# Enconder_Part3.net
KiCad netlist of a schematic drawn in Altium Designer
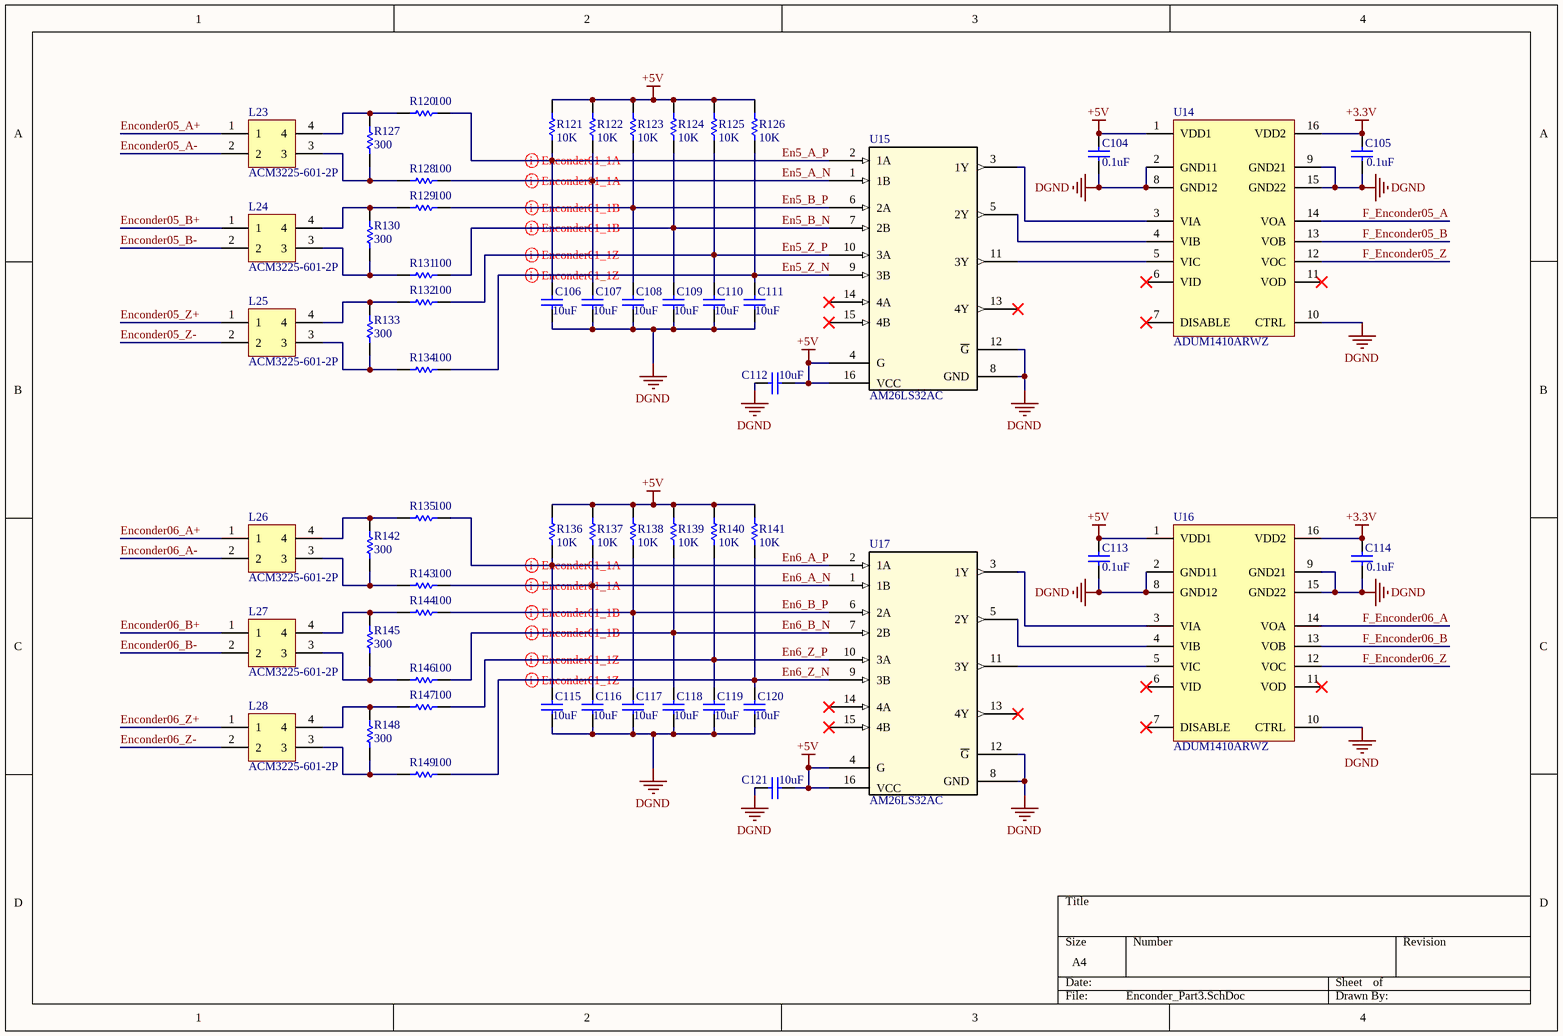
[diagram p0: Enconder_Part3.SchDoc]

(export (version "E")
  (design (tool "Eeschema 10.0.6"))
  (components
    (comp (ref "C104")
      (value "0.1uF")
      (footprint "1608[0603]")
      (description "Capacitor")
      (fields (field (name "Comment") "Cap") (field (name "PUBLISHER") "Altium Limited"))
      (libsource (lib "Miscellaneous Devices") (part "Cap"))
    )
    (comp (ref "C105")
      (value "0.1uF")
      (footprint "1608[0603]")
      (description "Capacitor")
      (fields (field (name "Comment") "Cap") (field (name "PUBLISHER") "Altium Limited"))
      (libsource (lib "Miscellaneous Devices") (part "Cap"))
    )
    (comp (ref "C106")
      (value "10uF")
      (footprint "1608[0603]")
      (description "Capacitor")
      (fields (field (name "Comment") "Cap") (field (name "PUBLISHER") "Altium Limited"))
      (libsource (lib "Miscellaneous Devices") (part "Cap"))
    )
    (comp (ref "C107")
      (value "10uF")
      (footprint "1608[0603]")
      (description "Capacitor")
      (fields (field (name "Comment") "Cap") (field (name "PUBLISHER") "Altium Limited"))
      (libsource (lib "Miscellaneous Devices") (part "Cap"))
    )
    (comp (ref "C108")
      (value "10uF")
      (footprint "1608[0603]")
      (description "Capacitor")
      (fields (field (name "Comment") "Cap") (field (name "PUBLISHER") "Altium Limited"))
      (libsource (lib "Miscellaneous Devices") (part "Cap"))
    )
    (comp (ref "C109")
      (value "10uF")
      (footprint "1608[0603]")
      (description "Capacitor")
      (fields (field (name "Comment") "Cap") (field (name "PUBLISHER") "Altium Limited"))
      (libsource (lib "Miscellaneous Devices") (part "Cap"))
    )
    (comp (ref "C110")
      (value "10uF")
      (footprint "1608[0603]")
      (description "Capacitor")
      (fields (field (name "Comment") "Cap") (field (name "PUBLISHER") "Altium Limited"))
      (libsource (lib "Miscellaneous Devices") (part "Cap"))
    )
    (comp (ref "C111")
      (value "10uF")
      (footprint "1608[0603]")
      (description "Capacitor")
      (fields (field (name "Comment") "Cap") (field (name "PUBLISHER") "Altium Limited"))
      (libsource (lib "Miscellaneous Devices") (part "Cap"))
    )
    (comp (ref "C112")
      (value "10uF")
      (footprint "1608[0603]")
      (description "Capacitor")
      (fields (field (name "Comment") "Cap") (field (name "PUBLISHER") "Altium Limited"))
      (libsource (lib "Miscellaneous Devices") (part "Cap"))
    )
    (comp (ref "C113")
      (value "0.1uF")
      (footprint "1608[0603]")
      (description "Capacitor")
      (fields (field (name "Comment") "Cap") (field (name "PUBLISHER") "Altium Limited"))
      (libsource (lib "Miscellaneous Devices") (part "Cap"))
    )
    (comp (ref "C114")
      (value "0.1uF")
      (footprint "1608[0603]")
      (description "Capacitor")
      (fields (field (name "Comment") "Cap") (field (name "PUBLISHER") "Altium Limited"))
      (libsource (lib "Miscellaneous Devices") (part "Cap"))
    )
    (comp (ref "C115")
      (value "10uF")
      (footprint "1608[0603]")
      (description "Capacitor")
      (fields (field (name "Comment") "Cap") (field (name "PUBLISHER") "Altium Limited"))
      (libsource (lib "Miscellaneous Devices") (part "Cap"))
    )
    (comp (ref "C116")
      (value "10uF")
      (footprint "1608[0603]")
      (description "Capacitor")
      (fields (field (name "Comment") "Cap") (field (name "PUBLISHER") "Altium Limited"))
      (libsource (lib "Miscellaneous Devices") (part "Cap"))
    )
    (comp (ref "C117")
      (value "10uF")
      (footprint "1608[0603]")
      (description "Capacitor")
      (fields (field (name "Comment") "Cap") (field (name "PUBLISHER") "Altium Limited"))
      (libsource (lib "Miscellaneous Devices") (part "Cap"))
    )
    (comp (ref "C118")
      (value "10uF")
      (footprint "1608[0603]")
      (description "Capacitor")
      (fields (field (name "Comment") "Cap") (field (name "PUBLISHER") "Altium Limited"))
      (libsource (lib "Miscellaneous Devices") (part "Cap"))
    )
    (comp (ref "C119")
      (value "10uF")
      (footprint "1608[0603]")
      (description "Capacitor")
      (fields (field (name "Comment") "Cap") (field (name "PUBLISHER") "Altium Limited"))
      (libsource (lib "Miscellaneous Devices") (part "Cap"))
    )
    (comp (ref "C120")
      (value "10uF")
      (footprint "1608[0603]")
      (description "Capacitor")
      (fields (field (name "Comment") "Cap") (field (name "PUBLISHER") "Altium Limited"))
      (libsource (lib "Miscellaneous Devices") (part "Cap"))
    )
    (comp (ref "C121")
      (value "10uF")
      (footprint "1608[0603]")
      (description "Capacitor")
      (fields (field (name "Comment") "Cap") (field (name "PUBLISHER") "Altium Limited"))
      (libsource (lib "Miscellaneous Devices") (part "Cap"))
    )
    (comp (ref "L23")
      (value "ACM3225-601-2P")
      (footprint "ACM3225-601-2P")
      (libsource (lib "DSP_FPGA_Lib") (part "ACM3225-601-2P"))
    )
    (comp (ref "L24")
      (value "ACM3225-601-2P")
      (footprint "ACM3225-601-2P")
      (libsource (lib "DSP_FPGA_Lib") (part "ACM3225-601-2P"))
    )
    (comp (ref "L25")
      (value "ACM3225-601-2P")
      (footprint "ACM3225-601-2P")
      (libsource (lib "DSP_FPGA_Lib") (part "ACM3225-601-2P"))
    )
    (comp (ref "L26")
      (value "ACM3225-601-2P")
      (footprint "ACM3225-601-2P")
      (libsource (lib "DSP_FPGA_Lib") (part "ACM3225-601-2P"))
    )
    (comp (ref "L27")
      (value "ACM3225-601-2P")
      (footprint "ACM3225-601-2P")
      (libsource (lib "DSP_FPGA_Lib") (part "ACM3225-601-2P"))
    )
    (comp (ref "L28")
      (value "ACM3225-601-2P")
      (footprint "ACM3225-601-2P")
      (libsource (lib "DSP_FPGA_Lib") (part "ACM3225-601-2P"))
    )
    (comp (ref "R120")
      (value "100")
      (footprint "1608[0603]")
      (description "Resistor")
      (fields (field (name "Comment") "Res1") (field (name "PUBLISHER") "Altium Limited"))
      (libsource (lib "Miscellaneous Devices") (part "Res1"))
    )
    (comp (ref "R121")
      (value "10K")
      (footprint "1608[0603]")
      (description "Resistor")
      (fields (field (name "Comment") "Res1") (field (name "PUBLISHER") "Altium Limited"))
      (libsource (lib "Miscellaneous Devices") (part "Res1"))
    )
    (comp (ref "R122")
      (value "10K")
      (footprint "1608[0603]")
      (description "Resistor")
      (fields (field (name "Comment") "Res1") (field (name "PUBLISHER") "Altium Limited"))
      (libsource (lib "Miscellaneous Devices") (part "Res1"))
    )
    (comp (ref "R123")
      (value "10K")
      (footprint "1608[0603]")
      (description "Resistor")
      (fields (field (name "Comment") "Res1") (field (name "PUBLISHER") "Altium Limited"))
      (libsource (lib "Miscellaneous Devices") (part "Res1"))
    )
    (comp (ref "R124")
      (value "10K")
      (footprint "1608[0603]")
      (description "Resistor")
      (fields (field (name "Comment") "Res1") (field (name "PUBLISHER") "Altium Limited"))
      (libsource (lib "Miscellaneous Devices") (part "Res1"))
    )
    (comp (ref "R125")
      (value "10K")
      (footprint "1608[0603]")
      (description "Resistor")
      (fields (field (name "Comment") "Res1") (field (name "PUBLISHER") "Altium Limited"))
      (libsource (lib "Miscellaneous Devices") (part "Res1"))
    )
    (comp (ref "R126")
      (value "10K")
      (footprint "1608[0603]")
      (description "Resistor")
      (fields (field (name "Comment") "Res1") (field (name "PUBLISHER") "Altium Limited"))
      (libsource (lib "Miscellaneous Devices") (part "Res1"))
    )
    (comp (ref "R127")
      (value "300")
      (footprint "1608[0603]")
      (description "Resistor")
      (fields (field (name "Comment") "Res1") (field (name "PUBLISHER") "Altium Limited"))
      (libsource (lib "Miscellaneous Devices") (part "Res1"))
    )
    (comp (ref "R128")
      (value "100")
      (footprint "1608[0603]")
      (description "Resistor")
      (fields (field (name "Comment") "Res1") (field (name "PUBLISHER") "Altium Limited"))
      (libsource (lib "Miscellaneous Devices") (part "Res1"))
    )
    (comp (ref "R129")
      (value "100")
      (footprint "1608[0603]")
      (description "Resistor")
      (fields (field (name "Comment") "Res1") (field (name "PUBLISHER") "Altium Limited"))
      (libsource (lib "Miscellaneous Devices") (part "Res1"))
    )
    (comp (ref "R130")
      (value "300")
      (footprint "1608[0603]")
      (description "Resistor")
      (fields (field (name "Comment") "Res1") (field (name "PUBLISHER") "Altium Limited"))
      (libsource (lib "Miscellaneous Devices") (part "Res1"))
    )
    (comp (ref "R131")
      (value "100")
      (footprint "1608[0603]")
      (description "Resistor")
      (fields (field (name "Comment") "Res1") (field (name "PUBLISHER") "Altium Limited"))
      (libsource (lib "Miscellaneous Devices") (part "Res1"))
    )
    (comp (ref "R132")
      (value "100")
      (footprint "1608[0603]")
      (description "Resistor")
      (fields (field (name "Comment") "Res1") (field (name "PUBLISHER") "Altium Limited"))
      (libsource (lib "Miscellaneous Devices") (part "Res1"))
    )
    (comp (ref "R133")
      (value "300")
      (footprint "1608[0603]")
      (description "Resistor")
      (fields (field (name "Comment") "Res1") (field (name "PUBLISHER") "Altium Limited"))
      (libsource (lib "Miscellaneous Devices") (part "Res1"))
    )
    (comp (ref "R134")
      (value "100")
      (footprint "1608[0603]")
      (description "Resistor")
      (fields (field (name "Comment") "Res1") (field (name "PUBLISHER") "Altium Limited"))
      (libsource (lib "Miscellaneous Devices") (part "Res1"))
    )
    (comp (ref "R135")
      (value "100")
      (footprint "1608[0603]")
      (description "Resistor")
      (fields (field (name "Comment") "Res1") (field (name "PUBLISHER") "Altium Limited"))
      (libsource (lib "Miscellaneous Devices") (part "Res1"))
    )
    (comp (ref "R136")
      (value "10K")
      (footprint "1608[0603]")
      (description "Resistor")
      (fields (field (name "Comment") "Res1") (field (name "PUBLISHER") "Altium Limited"))
      (libsource (lib "Miscellaneous Devices") (part "Res1"))
    )
    (comp (ref "R137")
      (value "10K")
      (footprint "1608[0603]")
      (description "Resistor")
      (fields (field (name "Comment") "Res1") (field (name "PUBLISHER") "Altium Limited"))
      (libsource (lib "Miscellaneous Devices") (part "Res1"))
    )
    (comp (ref "R138")
      (value "10K")
      (footprint "1608[0603]")
      (description "Resistor")
      (fields (field (name "Comment") "Res1") (field (name "PUBLISHER") "Altium Limited"))
      (libsource (lib "Miscellaneous Devices") (part "Res1"))
    )
    (comp (ref "R139")
      (value "10K")
      (footprint "1608[0603]")
      (description "Resistor")
      (fields (field (name "Comment") "Res1") (field (name "PUBLISHER") "Altium Limited"))
      (libsource (lib "Miscellaneous Devices") (part "Res1"))
    )
    (comp (ref "R140")
      (value "10K")
      (footprint "1608[0603]")
      (description "Resistor")
      (fields (field (name "Comment") "Res1") (field (name "PUBLISHER") "Altium Limited"))
      (libsource (lib "Miscellaneous Devices") (part "Res1"))
    )
    (comp (ref "R141")
      (value "10K")
      (footprint "1608[0603]")
      (description "Resistor")
      (fields (field (name "Comment") "Res1") (field (name "PUBLISHER") "Altium Limited"))
      (libsource (lib "Miscellaneous Devices") (part "Res1"))
    )
    (comp (ref "R142")
      (value "300")
      (footprint "1608[0603]")
      (description "Resistor")
      (fields (field (name "Comment") "Res1") (field (name "PUBLISHER") "Altium Limited"))
      (libsource (lib "Miscellaneous Devices") (part "Res1"))
    )
    (comp (ref "R143")
      (value "100")
      (footprint "1608[0603]")
      (description "Resistor")
      (fields (field (name "Comment") "Res1") (field (name "PUBLISHER") "Altium Limited"))
      (libsource (lib "Miscellaneous Devices") (part "Res1"))
    )
    (comp (ref "R144")
      (value "100")
      (footprint "1608[0603]")
      (description "Resistor")
      (fields (field (name "Comment") "Res1") (field (name "PUBLISHER") "Altium Limited"))
      (libsource (lib "Miscellaneous Devices") (part "Res1"))
    )
    (comp (ref "R145")
      (value "300")
      (footprint "1608[0603]")
      (description "Resistor")
      (fields (field (name "Comment") "Res1") (field (name "PUBLISHER") "Altium Limited"))
      (libsource (lib "Miscellaneous Devices") (part "Res1"))
    )
    (comp (ref "R146")
      (value "100")
      (footprint "1608[0603]")
      (description "Resistor")
      (fields (field (name "Comment") "Res1") (field (name "PUBLISHER") "Altium Limited"))
      (libsource (lib "Miscellaneous Devices") (part "Res1"))
    )
    (comp (ref "R147")
      (value "100")
      (footprint "1608[0603]")
      (description "Resistor")
      (fields (field (name "Comment") "Res1") (field (name "PUBLISHER") "Altium Limited"))
      (libsource (lib "Miscellaneous Devices") (part "Res1"))
    )
    (comp (ref "R148")
      (value "300")
      (footprint "1608[0603]")
      (description "Resistor")
      (fields (field (name "Comment") "Res1") (field (name "PUBLISHER") "Altium Limited"))
      (libsource (lib "Miscellaneous Devices") (part "Res1"))
    )
    (comp (ref "R149")
      (value "100")
      (footprint "1608[0603]")
      (description "Resistor")
      (fields (field (name "Comment") "Res1") (field (name "PUBLISHER") "Altium Limited"))
      (libsource (lib "Miscellaneous Devices") (part "Res1"))
    )
    (comp (ref "U14")
      (value "ADUM1410ARWZ")
      (footprint "ADUM1410ARWZ_SOIC")
      (libsource (lib "DSP_FPGA_Lib") (part "ADUM1410ARWZ"))
    )
    (comp (ref "U15")
      (value "AM26LS32AC")
      (footprint "AM26LS32AC_SOP")
      (libsource (lib "DSP_FPGA_Lib") (part "AM26LS32AC"))
    )
    (comp (ref "U16")
      (value "ADUM1410ARWZ")
      (footprint "ADUM1410ARWZ_SOIC")
      (libsource (lib "DSP_FPGA_Lib") (part "ADUM1410ARWZ"))
    )
    (comp (ref "U17")
      (value "AM26LS32AC")
      (footprint "AM26LS32AC_SOP")
      (libsource (lib "DSP_FPGA_Lib") (part "AM26LS32AC"))
    )
  )
  (nets
    (net (code "1") (name "+3.3V") (class "Default")
      (node (ref "C105") (pin "2") (pinfunction "2_2") (pintype "passive"))
      (node (ref "C114") (pin "2") (pinfunction "2_2") (pintype "passive"))
      (node (ref "U14") (pin "16") (pinfunction "VDD2_16") (pintype "passive"))
      (node (ref "U16") (pin "16") (pinfunction "VDD2_16") (pintype "passive"))
    )
    (net (code "2") (name "+5V") (class "Default")
      (node (ref "C104") (pin "2") (pinfunction "2_2") (pintype "passive"))
      (node (ref "C112") (pin "1") (pinfunction "1_1") (pintype "passive"))
      (node (ref "C113") (pin "2") (pinfunction "2_2") (pintype "passive"))
      (node (ref "C121") (pin "1") (pinfunction "1_1") (pintype "passive"))
      (node (ref "R121") (pin "2") (pinfunction "2_2") (pintype "passive"))
      (node (ref "R122") (pin "2") (pinfunction "2_2") (pintype "passive"))
      (node (ref "R123") (pin "2") (pinfunction "2_2") (pintype "passive"))
      (node (ref "R124") (pin "2") (pinfunction "2_2") (pintype "passive"))
      (node (ref "R125") (pin "2") (pinfunction "2_2") (pintype "passive"))
      (node (ref "R126") (pin "2") (pinfunction "2_2") (pintype "passive"))
      (node (ref "R136") (pin "2") (pinfunction "2_2") (pintype "passive"))
      (node (ref "R137") (pin "2") (pinfunction "2_2") (pintype "passive"))
      (node (ref "R138") (pin "2") (pinfunction "2_2") (pintype "passive"))
      (node (ref "R139") (pin "2") (pinfunction "2_2") (pintype "passive"))
      (node (ref "R140") (pin "2") (pinfunction "2_2") (pintype "passive"))
      (node (ref "R141") (pin "2") (pinfunction "2_2") (pintype "passive"))
      (node (ref "U14") (pin "1") (pinfunction "VDD1_1") (pintype "passive"))
      (node (ref "U15") (pin "16") (pinfunction "VCC_16") (pintype "power_in"))
      (node (ref "U15") (pin "4") (pinfunction "G_4") (pintype "passive"))
      (node (ref "U16") (pin "1") (pinfunction "VDD1_1") (pintype "passive"))
      (node (ref "U17") (pin "16") (pinfunction "VCC_16") (pintype "power_in"))
      (node (ref "U17") (pin "4") (pinfunction "G_4") (pintype "passive"))
    )
    (net (code "3") (name "/En5_A_N") (class "Default")
      (node (ref "C107") (pin "2") (pinfunction "2_2") (pintype "passive"))
      (node (ref "R122") (pin "1") (pinfunction "1_1") (pintype "passive"))
      (node (ref "R128") (pin "2") (pinfunction "2_2") (pintype "passive"))
      (node (ref "U15") (pin "1") (pinfunction "1B_1") (pintype "input"))
    )
    (net (code "4") (name "/En5_A_P") (class "Default")
      (node (ref "C106") (pin "2") (pinfunction "2_2") (pintype "passive"))
      (node (ref "R120") (pin "2") (pinfunction "2_2") (pintype "passive"))
      (node (ref "R121") (pin "1") (pinfunction "1_1") (pintype "passive"))
      (node (ref "U15") (pin "2") (pinfunction "1A_2") (pintype "input"))
    )
    (net (code "5") (name "/En5_B_N") (class "Default")
      (node (ref "C109") (pin "2") (pinfunction "2_2") (pintype "passive"))
      (node (ref "R124") (pin "1") (pinfunction "1_1") (pintype "passive"))
      (node (ref "R131") (pin "2") (pinfunction "2_2") (pintype "passive"))
      (node (ref "U15") (pin "7") (pinfunction "2B_7") (pintype "input"))
    )
    (net (code "6") (name "/En5_B_P") (class "Default")
      (node (ref "C108") (pin "2") (pinfunction "2_2") (pintype "passive"))
      (node (ref "R123") (pin "1") (pinfunction "1_1") (pintype "passive"))
      (node (ref "R129") (pin "2") (pinfunction "2_2") (pintype "passive"))
      (node (ref "U15") (pin "6") (pinfunction "2A_6") (pintype "input"))
    )
    (net (code "7") (name "/En5_Z_N") (class "Default")
      (node (ref "C111") (pin "2") (pinfunction "2_2") (pintype "passive"))
      (node (ref "R126") (pin "1") (pinfunction "1_1") (pintype "passive"))
      (node (ref "R134") (pin "2") (pinfunction "2_2") (pintype "passive"))
      (node (ref "U15") (pin "9") (pinfunction "3B_9") (pintype "input"))
    )
    (net (code "8") (name "/En5_Z_P") (class "Default")
      (node (ref "C110") (pin "2") (pinfunction "2_2") (pintype "passive"))
      (node (ref "R125") (pin "1") (pinfunction "1_1") (pintype "passive"))
      (node (ref "R132") (pin "2") (pinfunction "2_2") (pintype "passive"))
      (node (ref "U15") (pin "10") (pinfunction "3A_10") (pintype "input"))
    )
    (net (code "9") (name "/En6_A_N") (class "Default")
      (node (ref "C116") (pin "2") (pinfunction "2_2") (pintype "passive"))
      (node (ref "R137") (pin "1") (pinfunction "1_1") (pintype "passive"))
      (node (ref "R143") (pin "2") (pinfunction "2_2") (pintype "passive"))
      (node (ref "U17") (pin "1") (pinfunction "1B_1") (pintype "input"))
    )
    (net (code "10") (name "/En6_A_P") (class "Default")
      (node (ref "C115") (pin "2") (pinfunction "2_2") (pintype "passive"))
      (node (ref "R135") (pin "2") (pinfunction "2_2") (pintype "passive"))
      (node (ref "R136") (pin "1") (pinfunction "1_1") (pintype "passive"))
      (node (ref "U17") (pin "2") (pinfunction "1A_2") (pintype "input"))
    )
    (net (code "11") (name "/En6_B_N") (class "Default")
      (node (ref "C118") (pin "2") (pinfunction "2_2") (pintype "passive"))
      (node (ref "R139") (pin "1") (pinfunction "1_1") (pintype "passive"))
      (node (ref "R146") (pin "2") (pinfunction "2_2") (pintype "passive"))
      (node (ref "U17") (pin "7") (pinfunction "2B_7") (pintype "input"))
    )
    (net (code "12") (name "/En6_B_P") (class "Default")
      (node (ref "C117") (pin "2") (pinfunction "2_2") (pintype "passive"))
      (node (ref "R138") (pin "1") (pinfunction "1_1") (pintype "passive"))
      (node (ref "R144") (pin "2") (pinfunction "2_2") (pintype "passive"))
      (node (ref "U17") (pin "6") (pinfunction "2A_6") (pintype "input"))
    )
    (net (code "13") (name "/En6_Z_N") (class "Default")
      (node (ref "C120") (pin "2") (pinfunction "2_2") (pintype "passive"))
      (node (ref "R141") (pin "1") (pinfunction "1_1") (pintype "passive"))
      (node (ref "R149") (pin "2") (pinfunction "2_2") (pintype "passive"))
      (node (ref "U17") (pin "9") (pinfunction "3B_9") (pintype "input"))
    )
    (net (code "14") (name "/En6_Z_P") (class "Default")
      (node (ref "C119") (pin "2") (pinfunction "2_2") (pintype "passive"))
      (node (ref "R140") (pin "1") (pinfunction "1_1") (pintype "passive"))
      (node (ref "R147") (pin "2") (pinfunction "2_2") (pintype "passive"))
      (node (ref "U17") (pin "10") (pinfunction "3A_10") (pintype "input"))
    )
    (net (code "15") (name "/Enconder05_A+") (class "Default")
      (node (ref "L23") (pin "1") (pinfunction "1_1") (pintype "passive"))
    )
    (net (code "16") (name "/Enconder05_A-") (class "Default")
      (node (ref "L23") (pin "2") (pinfunction "2_2") (pintype "passive"))
    )
    (net (code "17") (name "/Enconder05_B+") (class "Default")
      (node (ref "L24") (pin "1") (pinfunction "1_1") (pintype "passive"))
    )
    (net (code "18") (name "/Enconder05_B-") (class "Default")
      (node (ref "L24") (pin "2") (pinfunction "2_2") (pintype "passive"))
    )
    (net (code "19") (name "/Enconder05_Z+") (class "Default")
      (node (ref "L25") (pin "1") (pinfunction "1_1") (pintype "passive"))
    )
    (net (code "20") (name "/Enconder05_Z-") (class "Default")
      (node (ref "L25") (pin "2") (pinfunction "2_2") (pintype "passive"))
    )
    (net (code "21") (name "/Enconder06_A+") (class "Default")
      (node (ref "L26") (pin "1") (pinfunction "1_1") (pintype "passive"))
    )
    (net (code "22") (name "/Enconder06_A-") (class "Default")
      (node (ref "L26") (pin "2") (pinfunction "2_2") (pintype "passive"))
    )
    (net (code "23") (name "/Enconder06_B+") (class "Default")
      (node (ref "L27") (pin "1") (pinfunction "1_1") (pintype "passive"))
    )
    (net (code "24") (name "/Enconder06_B-") (class "Default")
      (node (ref "L27") (pin "2") (pinfunction "2_2") (pintype "passive"))
    )
    (net (code "25") (name "/Enconder06_Z+") (class "Default")
      (node (ref "L28") (pin "1") (pinfunction "1_1") (pintype "passive"))
    )
    (net (code "26") (name "/Enconder06_Z-") (class "Default")
      (node (ref "L28") (pin "2") (pinfunction "2_2") (pintype "passive"))
    )
    (net (code "27") (name "/F_Enconder05_A") (class "Default")
      (node (ref "U14") (pin "14") (pinfunction "VOA_14") (pintype "passive"))
    )
    (net (code "28") (name "/F_Enconder05_B") (class "Default")
      (node (ref "U14") (pin "13") (pinfunction "VOB_13") (pintype "passive"))
    )
    (net (code "29") (name "/F_Enconder05_Z") (class "Default")
      (node (ref "U14") (pin "12") (pinfunction "VOC_12") (pintype "passive"))
    )
    (net (code "30") (name "/F_Enconder06_A") (class "Default")
      (node (ref "U16") (pin "14") (pinfunction "VOA_14") (pintype "passive"))
    )
    (net (code "31") (name "/F_Enconder06_B") (class "Default")
      (node (ref "U16") (pin "13") (pinfunction "VOB_13") (pintype "passive"))
    )
    (net (code "32") (name "/F_Enconder06_Z") (class "Default")
      (node (ref "U16") (pin "12") (pinfunction "VOC_12") (pintype "passive"))
    )
    (net (code "33") (name "DGND") (class "Default")
      (node (ref "C104") (pin "1") (pinfunction "1_1") (pintype "passive"))
      (node (ref "C105") (pin "1") (pinfunction "1_1") (pintype "passive"))
      (node (ref "C106") (pin "1") (pinfunction "1_1") (pintype "passive"))
      (node (ref "C107") (pin "1") (pinfunction "1_1") (pintype "passive"))
      (node (ref "C108") (pin "1") (pinfunction "1_1") (pintype "passive"))
      (node (ref "C109") (pin "1") (pinfunction "1_1") (pintype "passive"))
      (node (ref "C110") (pin "1") (pinfunction "1_1") (pintype "passive"))
      (node (ref "C111") (pin "1") (pinfunction "1_1") (pintype "passive"))
      (node (ref "C112") (pin "2") (pinfunction "2_2") (pintype "passive"))
      (node (ref "C113") (pin "1") (pinfunction "1_1") (pintype "passive"))
      (node (ref "C114") (pin "1") (pinfunction "1_1") (pintype "passive"))
      (node (ref "C115") (pin "1") (pinfunction "1_1") (pintype "passive"))
      (node (ref "C116") (pin "1") (pinfunction "1_1") (pintype "passive"))
      (node (ref "C117") (pin "1") (pinfunction "1_1") (pintype "passive"))
      (node (ref "C118") (pin "1") (pinfunction "1_1") (pintype "passive"))
      (node (ref "C119") (pin "1") (pinfunction "1_1") (pintype "passive"))
      (node (ref "C120") (pin "1") (pinfunction "1_1") (pintype "passive"))
      (node (ref "C121") (pin "2") (pinfunction "2_2") (pintype "passive"))
      (node (ref "U14") (pin "10") (pinfunction "CTRL_10") (pintype "passive"))
      (node (ref "U14") (pin "15") (pinfunction "GND22_15") (pintype "passive"))
      (node (ref "U14") (pin "2") (pinfunction "GND11_2") (pintype "passive"))
      (node (ref "U14") (pin "8") (pinfunction "GND12_8") (pintype "passive"))
      (node (ref "U14") (pin "9") (pinfunction "GND21_9") (pintype "passive"))
      (node (ref "U15") (pin "12") (pinfunction "~{G}_12") (pintype "passive"))
      (node (ref "U15") (pin "8") (pinfunction "GND_8") (pintype "power_in"))
      (node (ref "U16") (pin "10") (pinfunction "CTRL_10") (pintype "passive"))
      (node (ref "U16") (pin "15") (pinfunction "GND22_15") (pintype "passive"))
      (node (ref "U16") (pin "2") (pinfunction "GND11_2") (pintype "passive"))
      (node (ref "U16") (pin "8") (pinfunction "GND12_8") (pintype "passive"))
      (node (ref "U16") (pin "9") (pinfunction "GND21_9") (pintype "passive"))
      (node (ref "U17") (pin "12") (pinfunction "~{G}_12") (pintype "passive"))
      (node (ref "U17") (pin "8") (pinfunction "GND_8") (pintype "power_in"))
    )
    (net (code "34") (name "Net-(L23-Pad3)") (class "Default")
      (node (ref "L23") (pin "3") (pinfunction "3_3") (pintype "passive"))
      (node (ref "R127") (pin "1") (pinfunction "1_1") (pintype "passive"))
      (node (ref "R128") (pin "1") (pinfunction "1_1") (pintype "passive"))
    )
    (net (code "35") (name "Net-(L23-Pad4)") (class "Default")
      (node (ref "L23") (pin "4") (pinfunction "4_4") (pintype "passive"))
      (node (ref "R120") (pin "1") (pinfunction "1_1") (pintype "passive"))
      (node (ref "R127") (pin "2") (pinfunction "2_2") (pintype "passive"))
    )
    (net (code "36") (name "Net-(L24-Pad3)") (class "Default")
      (node (ref "L24") (pin "3") (pinfunction "3_3") (pintype "passive"))
      (node (ref "R130") (pin "1") (pinfunction "1_1") (pintype "passive"))
      (node (ref "R131") (pin "1") (pinfunction "1_1") (pintype "passive"))
    )
    (net (code "37") (name "Net-(L24-Pad4)") (class "Default")
      (node (ref "L24") (pin "4") (pinfunction "4_4") (pintype "passive"))
      (node (ref "R129") (pin "1") (pinfunction "1_1") (pintype "passive"))
      (node (ref "R130") (pin "2") (pinfunction "2_2") (pintype "passive"))
    )
    (net (code "38") (name "Net-(L25-Pad3)") (class "Default")
      (node (ref "L25") (pin "3") (pinfunction "3_3") (pintype "passive"))
      (node (ref "R133") (pin "1") (pinfunction "1_1") (pintype "passive"))
      (node (ref "R134") (pin "1") (pinfunction "1_1") (pintype "passive"))
    )
    (net (code "39") (name "Net-(L25-Pad4)") (class "Default")
      (node (ref "L25") (pin "4") (pinfunction "4_4") (pintype "passive"))
      (node (ref "R132") (pin "1") (pinfunction "1_1") (pintype "passive"))
      (node (ref "R133") (pin "2") (pinfunction "2_2") (pintype "passive"))
    )
    (net (code "40") (name "Net-(L26-Pad3)") (class "Default")
      (node (ref "L26") (pin "3") (pinfunction "3_3") (pintype "passive"))
      (node (ref "R142") (pin "1") (pinfunction "1_1") (pintype "passive"))
      (node (ref "R143") (pin "1") (pinfunction "1_1") (pintype "passive"))
    )
    (net (code "41") (name "Net-(L26-Pad4)") (class "Default")
      (node (ref "L26") (pin "4") (pinfunction "4_4") (pintype "passive"))
      (node (ref "R135") (pin "1") (pinfunction "1_1") (pintype "passive"))
      (node (ref "R142") (pin "2") (pinfunction "2_2") (pintype "passive"))
    )
    (net (code "42") (name "Net-(L27-Pad3)") (class "Default")
      (node (ref "L27") (pin "3") (pinfunction "3_3") (pintype "passive"))
      (node (ref "R145") (pin "1") (pinfunction "1_1") (pintype "passive"))
      (node (ref "R146") (pin "1") (pinfunction "1_1") (pintype "passive"))
    )
    (net (code "43") (name "Net-(L27-Pad4)") (class "Default")
      (node (ref "L27") (pin "4") (pinfunction "4_4") (pintype "passive"))
      (node (ref "R144") (pin "1") (pinfunction "1_1") (pintype "passive"))
      (node (ref "R145") (pin "2") (pinfunction "2_2") (pintype "passive"))
    )
    (net (code "44") (name "Net-(L28-Pad3)") (class "Default")
      (node (ref "L28") (pin "3") (pinfunction "3_3") (pintype "passive"))
      (node (ref "R148") (pin "1") (pinfunction "1_1") (pintype "passive"))
      (node (ref "R149") (pin "1") (pinfunction "1_1") (pintype "passive"))
    )
    (net (code "45") (name "Net-(L28-Pad4)") (class "Default")
      (node (ref "L28") (pin "4") (pinfunction "4_4") (pintype "passive"))
      (node (ref "R147") (pin "1") (pinfunction "1_1") (pintype "passive"))
      (node (ref "R148") (pin "2") (pinfunction "2_2") (pintype "passive"))
    )
    (net (code "46") (name "Net-(U14-VIA)") (class "Default")
      (node (ref "U14") (pin "3") (pinfunction "VIA_3") (pintype "passive"))
      (node (ref "U15") (pin "3") (pinfunction "1Y_3") (pintype "output"))
    )
    (net (code "47") (name "Net-(U14-VIB)") (class "Default")
      (node (ref "U14") (pin "4") (pinfunction "VIB_4") (pintype "passive"))
      (node (ref "U15") (pin "5") (pinfunction "2Y_5") (pintype "output"))
    )
    (net (code "48") (name "Net-(U14-VIC)") (class "Default")
      (node (ref "U14") (pin "5") (pinfunction "VIC_5") (pintype "passive"))
      (node (ref "U15") (pin "11") (pinfunction "3Y_11") (pintype "output"))
    )
    (net (code "49") (name "Net-(U16-VIA)") (class "Default")
      (node (ref "U16") (pin "3") (pinfunction "VIA_3") (pintype "passive"))
      (node (ref "U17") (pin "3") (pinfunction "1Y_3") (pintype "output"))
    )
    (net (code "50") (name "Net-(U16-VIB)") (class "Default")
      (node (ref "U16") (pin "4") (pinfunction "VIB_4") (pintype "passive"))
      (node (ref "U17") (pin "5") (pinfunction "2Y_5") (pintype "output"))
    )
    (net (code "51") (name "Net-(U16-VIC)") (class "Default")
      (node (ref "U16") (pin "5") (pinfunction "VIC_5") (pintype "passive"))
      (node (ref "U17") (pin "11") (pinfunction "3Y_11") (pintype "output"))
    )
    (net (code "52") (name "unconnected-(U14-DISABLE-Pad7)") (class "Default")
      (node (ref "U14") (pin "7") (pinfunction "DISABLE_7") (pintype "passive+no_connect"))
    )
    (net (code "53") (name "unconnected-(U14-VID-Pad6)") (class "Default")
      (node (ref "U14") (pin "6") (pinfunction "VID_6") (pintype "passive+no_connect"))
    )
    (net (code "54") (name "unconnected-(U14-VOD-Pad11)") (class "Default")
      (node (ref "U14") (pin "11") (pinfunction "VOD_11") (pintype "passive+no_connect"))
    )
    (net (code "55") (name "unconnected-(U15-4A-Pad14)") (class "Default")
      (node (ref "U15") (pin "14") (pinfunction "4A_14") (pintype "input+no_connect"))
    )
    (net (code "56") (name "unconnected-(U15-4B-Pad15)") (class "Default")
      (node (ref "U15") (pin "15") (pinfunction "4B_15") (pintype "input+no_connect"))
    )
    (net (code "57") (name "unconnected-(U15-4Y-Pad13)") (class "Default")
      (node (ref "U15") (pin "13") (pinfunction "4Y_13") (pintype "output+no_connect"))
    )
    (net (code "58") (name "unconnected-(U16-DISABLE-Pad7)") (class "Default")
      (node (ref "U16") (pin "7") (pinfunction "DISABLE_7") (pintype "passive+no_connect"))
    )
    (net (code "59") (name "unconnected-(U16-VID-Pad6)") (class "Default")
      (node (ref "U16") (pin "6") (pinfunction "VID_6") (pintype "passive+no_connect"))
    )
    (net (code "60") (name "unconnected-(U16-VOD-Pad11)") (class "Default")
      (node (ref "U16") (pin "11") (pinfunction "VOD_11") (pintype "passive+no_connect"))
    )
    (net (code "61") (name "unconnected-(U17-4A-Pad14)") (class "Default")
      (node (ref "U17") (pin "14") (pinfunction "4A_14") (pintype "input+no_connect"))
    )
    (net (code "62") (name "unconnected-(U17-4B-Pad15)") (class "Default")
      (node (ref "U17") (pin "15") (pinfunction "4B_15") (pintype "input+no_connect"))
    )
    (net (code "63") (name "unconnected-(U17-4Y-Pad13)") (class "Default")
      (node (ref "U17") (pin "13") (pinfunction "4Y_13") (pintype "output+no_connect"))
    )
  )
)
